# GPRS_A7.net
KiCad netlist of a schematic drawn in EAGLE
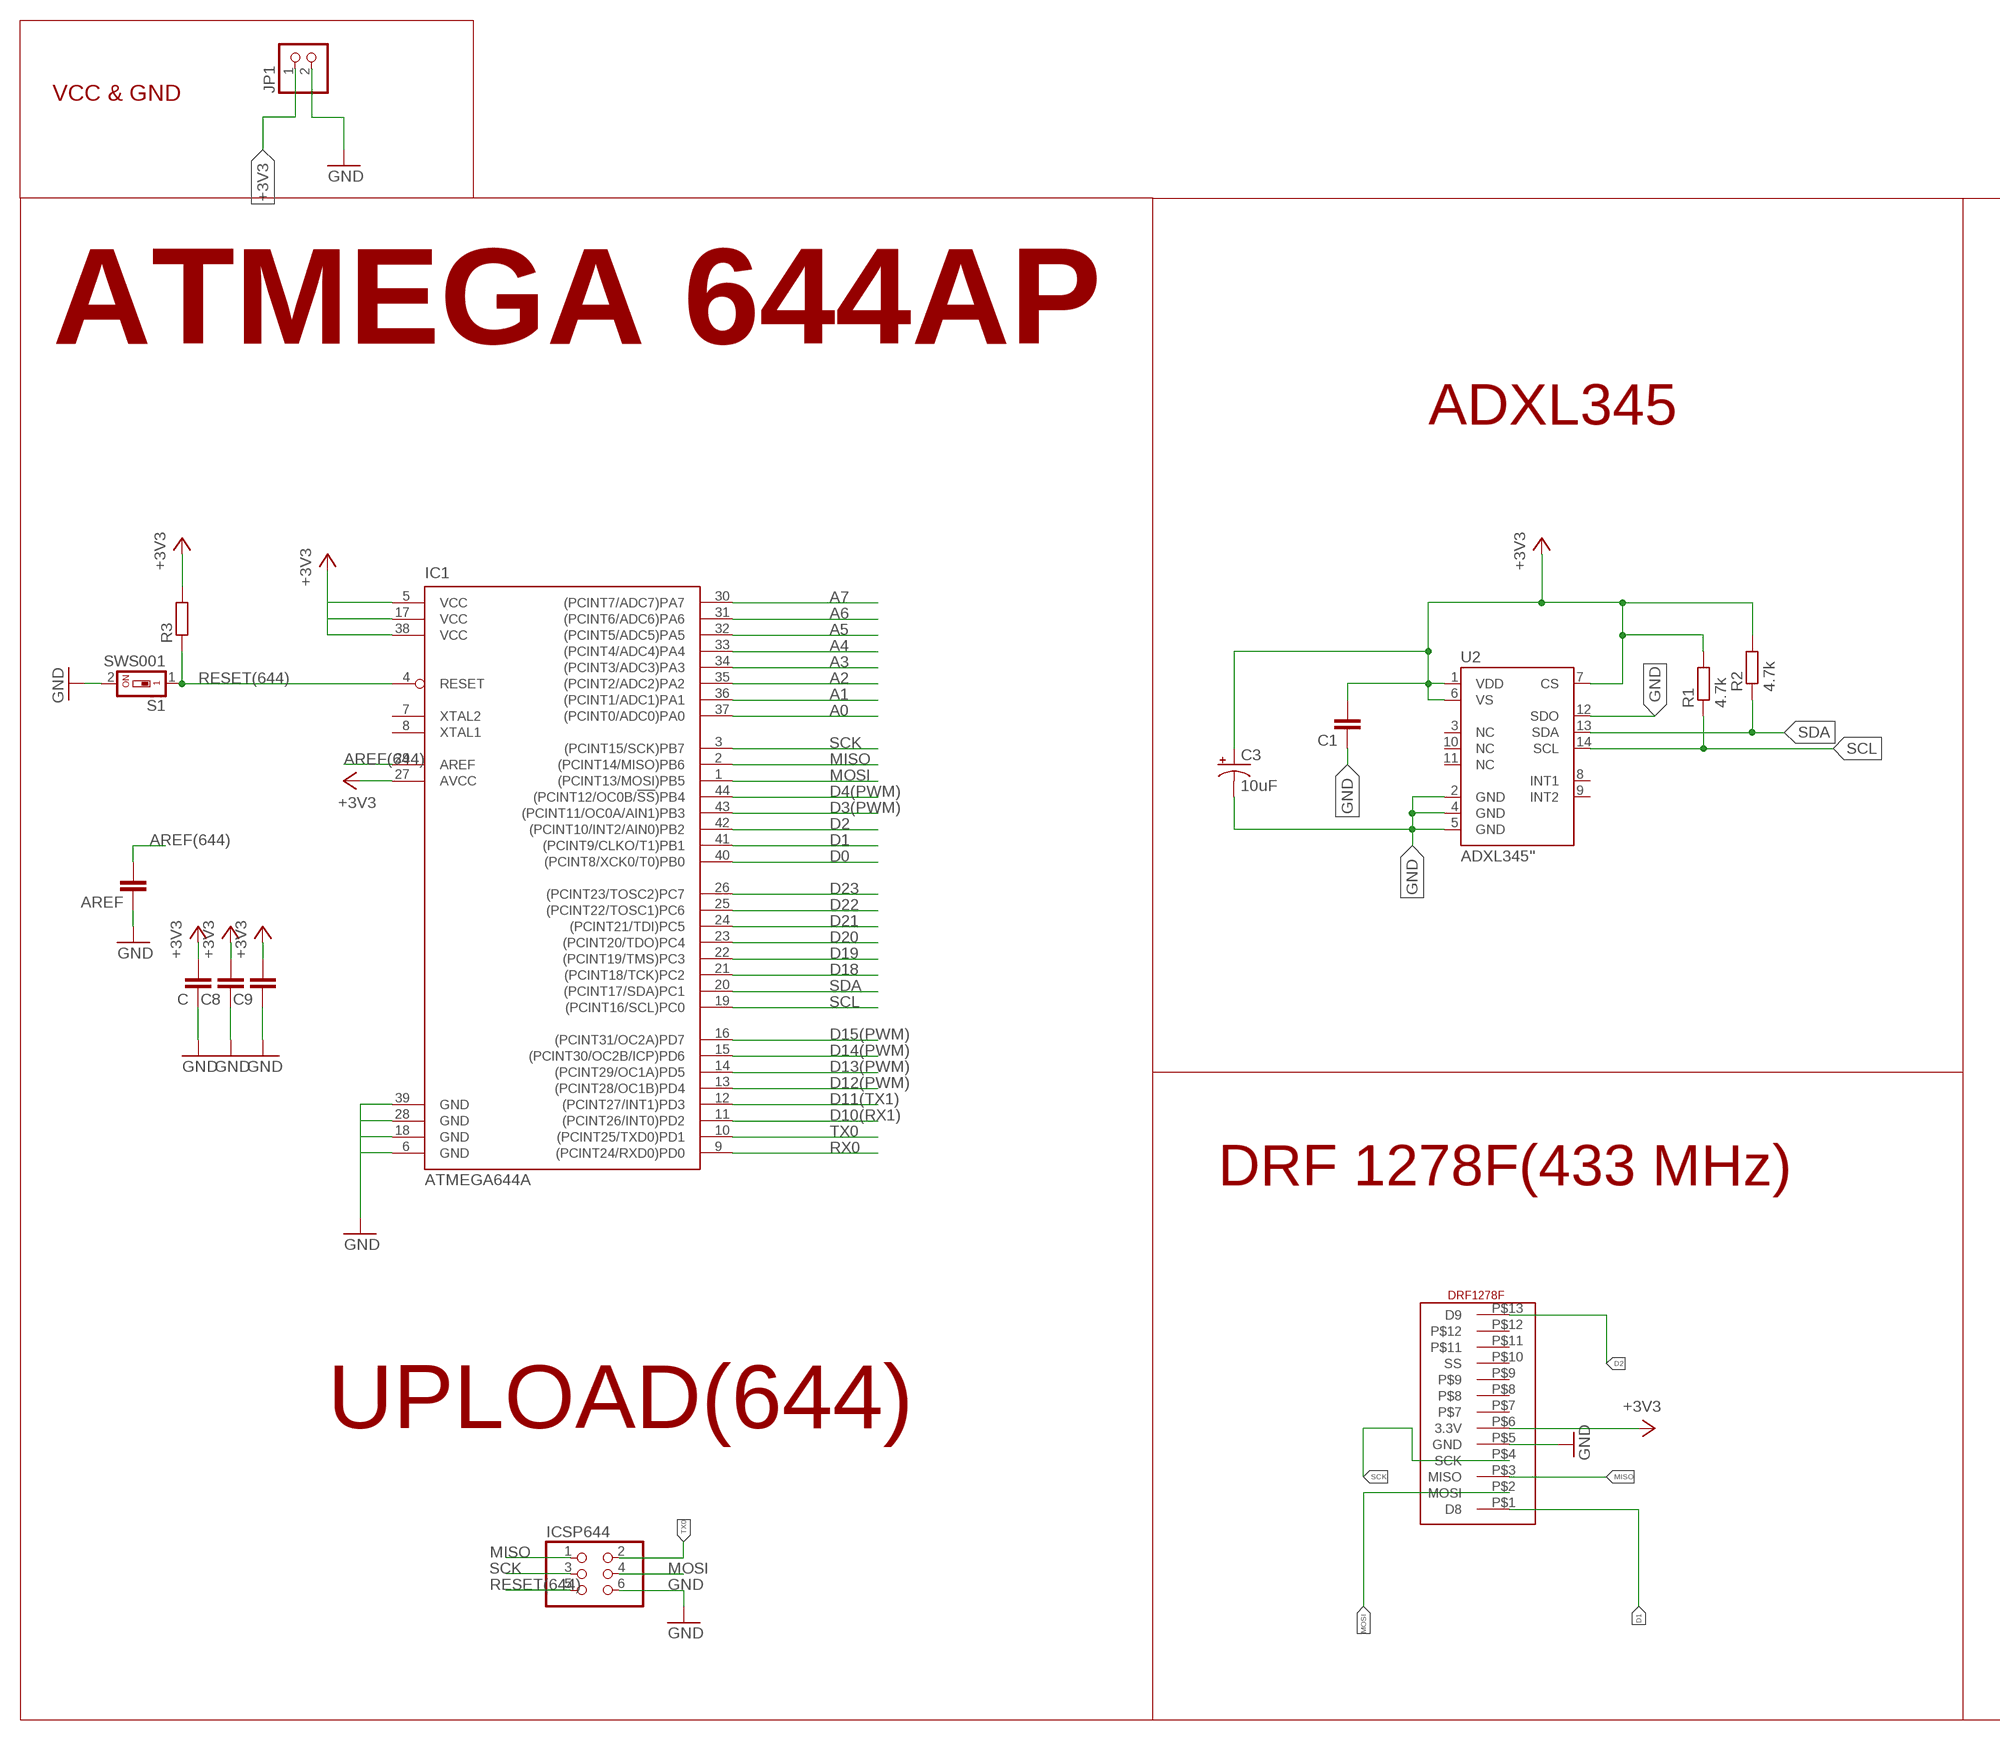
[diagram p0: schematic, sheet 1, part 1 of 2]
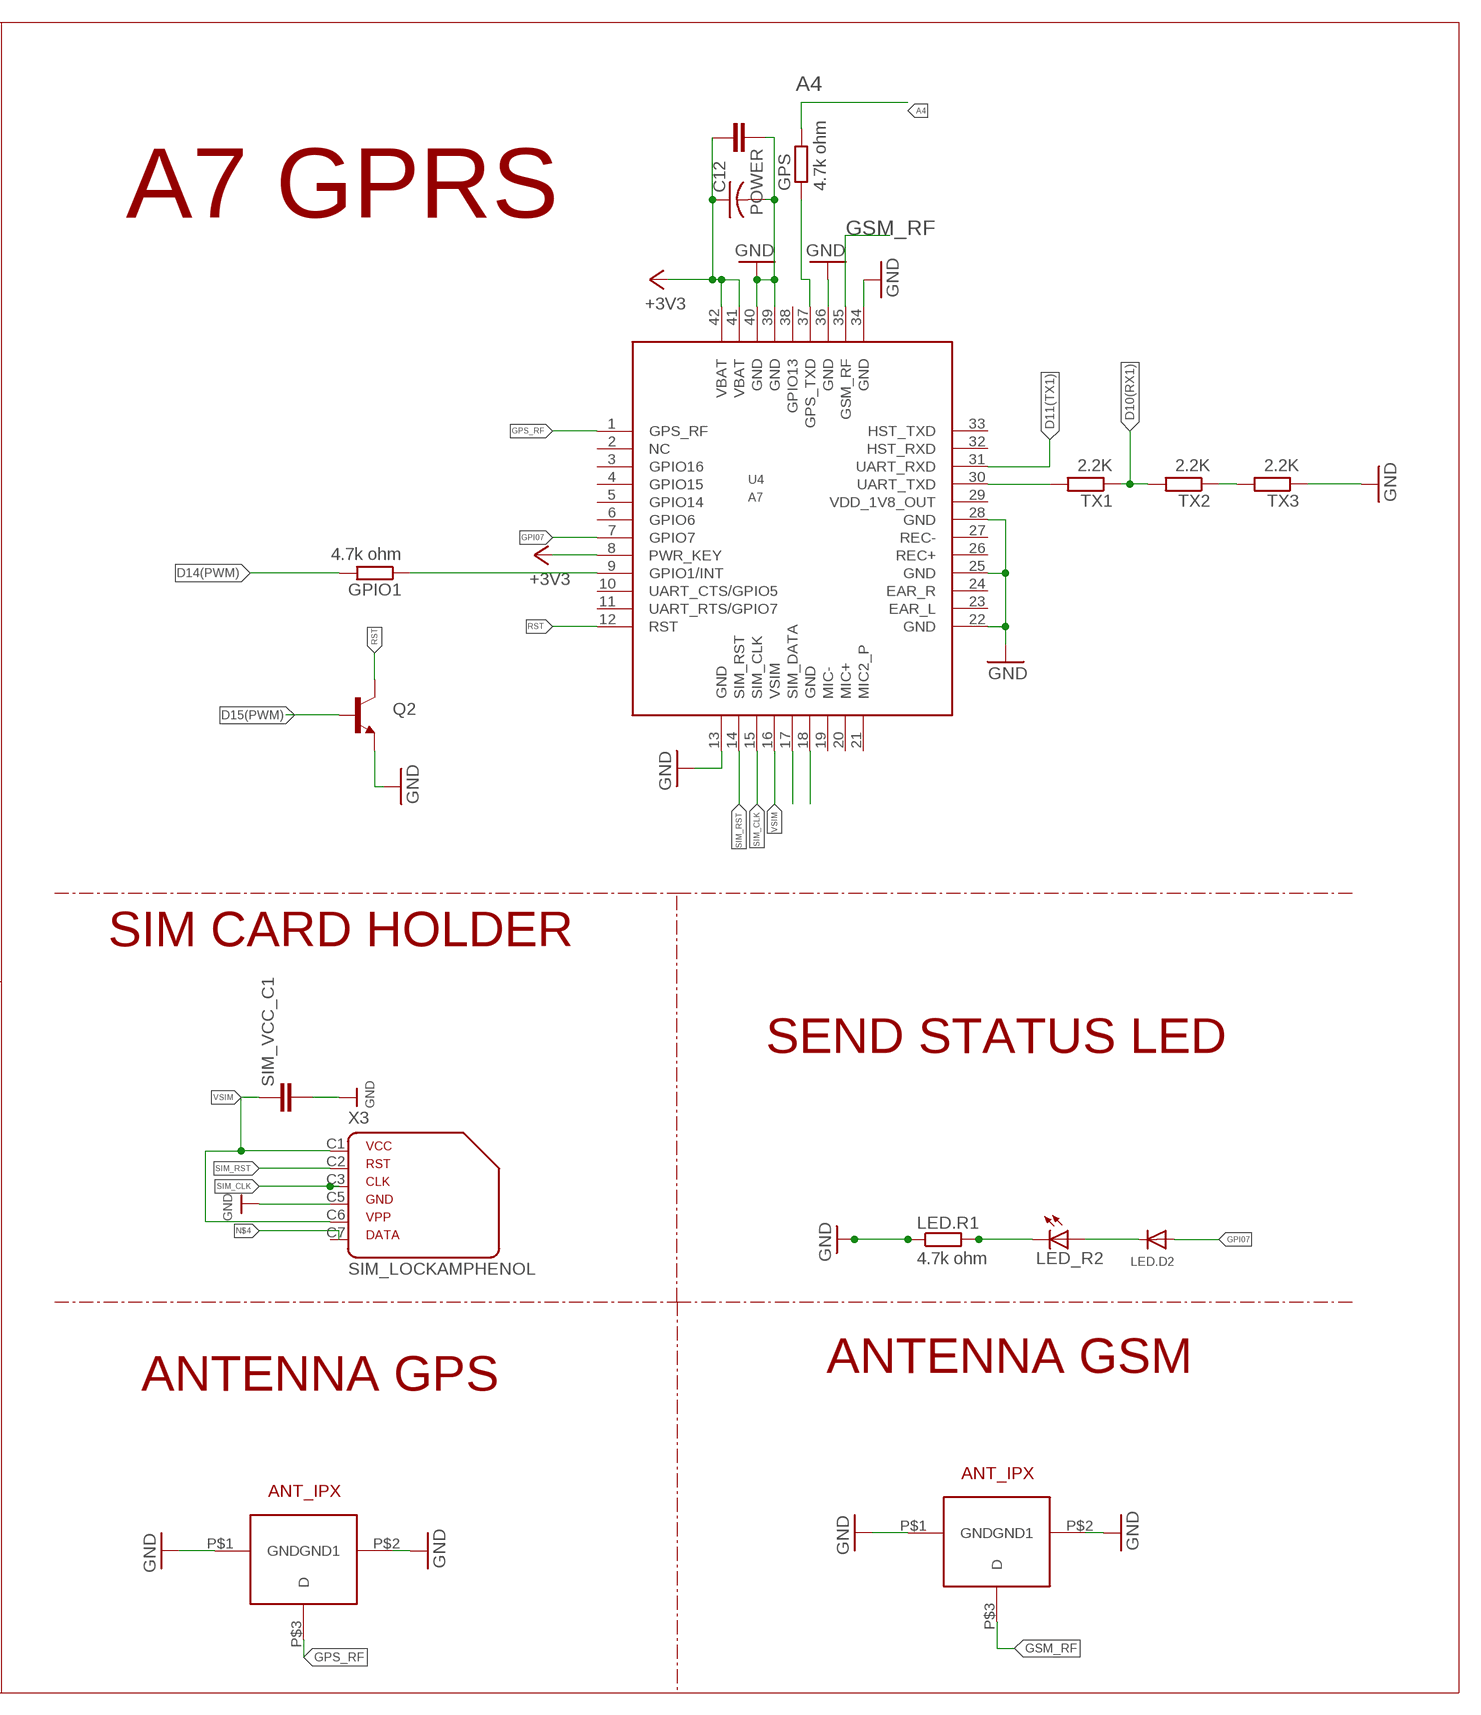
[diagram p1: schematic, sheet 1, part 2 of 2]

(export (version "E")
  (design (tool "Eeschema 10.0.6"))
  (components
    (comp (ref "AREF")
      (value "100nF")
      (footprint "eagle-import:C0805")
      (libsource (lib "eagle-import") (part "C-EUC0805"))
    )
    (comp (ref "C")
      (value "22 uF")
      (footprint "eagle-import:C0805")
      (libsource (lib "eagle-import") (part "C-EUC0805"))
    )
    (comp (ref "C1")
      (value "0.1uF")
      (footprint "eagle-import:C0805")
      (libsource (lib "eagle-import") (part "C-EUC0805"))
    )
    (comp (ref "C3")
      (value "10uF")
      (footprint "eagle-import:EIA3216")
      (libsource (lib "eagle-import") (part "CAP_POL1206"))
    )
    (comp (ref "C8")
      (value "100nF")
      (footprint "eagle-import:C0805")
      (libsource (lib "eagle-import") (part "C-EUC0805"))
    )
    (comp (ref "C9")
      (value "100nF")
      (footprint "eagle-import:C0805")
      (libsource (lib "eagle-import") (part "C-EUC0805"))
    )
    (comp (ref "C12")
      (value "C-US025-024X044")
      (footprint "eagle-import:C025-024X044")
      (libsource (lib "eagle-import") (part "C-US025-024X044"))
    )
    (comp (ref "GPIO1")
      (value "4.7k ohm")
      (footprint "eagle-import:R0805")
      (libsource (lib "eagle-import") (part "R-EU_R0805"))
    )
    (comp (ref "GPS")
      (value "4.7k ohm")
      (footprint "eagle-import:R0805")
      (libsource (lib "eagle-import") (part "R-EU_R0805"))
    )
    (comp (ref "IC1")
      (value "ATMEGA644A")
      (footprint "eagle-import:TQFP44")
      (fields (field (name "MPN") "ATMEGA644PV-10AU"))
      (libsource (lib "eagle-import") (part "ATMEGA644A"))
    )
    (comp (ref "ICSP644")
      (value "PINHD-2X3")
      (footprint "eagle-import:2X03")
      (libsource (lib "eagle-import") (part "PINHD-2X3"))
    )
    (comp (ref "JP1")
      (value "PINHD-1X2")
      (footprint "eagle-import:1X02")
      (libsource (lib "eagle-import") (part "PINHD-1X2"))
    )
    (comp (ref "LED.D2")
      (value "DIODESOD-123")
      (footprint "eagle-import:SOD-123")
      (libsource (lib "eagle-import") (part "DIODESOD-123"))
    )
    (comp (ref "LED.R1")
      (value "4.7k ohm")
      (footprint "eagle-import:R0805")
      (libsource (lib "eagle-import") (part "R-EU_R0805"))
    )
    (comp (ref "LED_R2")
      (value "LEDCHIP-LED0805")
      (footprint "eagle-import:CHIP-LED0805")
      (libsource (lib "eagle-import") (part "LEDCHIP-LED0805"))
    )
    (comp (ref "POWER")
      (value "100nF")
      (footprint "eagle-import:C0805")
      (libsource (lib "eagle-import") (part "C-EUC0805"))
    )
    (comp (ref "Q2")
      (value "TRANSISTOR_NPNSOT23-3")
      (footprint "eagle-import:SOT23-3")
      (libsource (lib "eagle-import") (part "TRANSISTOR_NPNSOT23-3"))
    )
    (comp (ref "R1")
      (value "4.7k")
      (footprint "eagle-import:R0805")
      (libsource (lib "eagle-import") (part "R-EU_R0805"))
    )
    (comp (ref "R2")
      (value "4.7k")
      (footprint "eagle-import:R0805")
      (libsource (lib "eagle-import") (part "R-EU_R0805"))
    )
    (comp (ref "R3")
      (value "R-EU_R0805")
      (footprint "eagle-import:R0805")
      (libsource (lib "eagle-import") (part "R-EU_R0805"))
    )
    (comp (ref "S1")
      (value "SWS001")
      (footprint "eagle-import:SMS-001")
      (libsource (lib "eagle-import") (part "SWS001"))
    )
    (comp (ref "SIM_VCC_C1")
      (value "100nF")
      (footprint "eagle-import:C0805")
      (libsource (lib "eagle-import") (part "C-EUC0805"))
    )
    (comp (ref "TX1")
      (value "2.2K")
      (footprint "eagle-import:R0805")
      (libsource (lib "eagle-import") (part "R-EU_R0805"))
    )
    (comp (ref "TX2")
      (value "2.2K")
      (footprint "eagle-import:R0805")
      (libsource (lib "eagle-import") (part "R-EU_R0805"))
    )
    (comp (ref "TX3")
      (value "2.2K")
      (footprint "eagle-import:R0805")
      (libsource (lib "eagle-import") (part "R-EU_R0805"))
    )
    (comp (ref "U$1")
      (value "DRF1278F")
      (footprint "eagle-import:DIP13")
      (libsource (lib "eagle-import") (part "DRF1278F"))
    )
    (comp (ref "U$2")
      (value "ANTENNA_IPX")
      (footprint "eagle-import:SMD3")
      (libsource (lib "eagle-import") (part "ANTENNA_IPX"))
    )
    (comp (ref "U$9")
      (value "ANTENNA_IPX")
      (footprint "eagle-import:SMD3")
      (libsource (lib "eagle-import") (part "ANTENNA_IPX"))
    )
    (comp (ref "U2")
      (value "ADXL345\"")
      (footprint "eagle-import:ADXL3451_1")
      (libsource (lib "eagle-import") (part "ADXL345{dblquote}"))
    )
    (comp (ref "U4") (value "A7") (footprint "eagle-import:A7") (libsource (lib "eagle-import") (part "A7")))
    (comp (ref "X3")
      (value "SIM_LOCKAMPHENOL")
      (footprint "eagle-import:C707_10M006_512_2")
      (libsource (lib "eagle-import") (part "SIM_LOCKAMPHENOL"))
    )
  )
  (nets
    (net (code "1") (name "+3V3") (class "Default")
      (node (ref "C") (pin "2") (pinfunction "2_2") (pintype "passive"))
      (node (ref "C1") (pin "2") (pinfunction "2_2") (pintype "passive"))
      (node (ref "C12") (pin "1") (pinfunction "1_1") (pintype "passive"))
      (node (ref "C3") (pin "A") (pinfunction "+_A") (pintype "passive"))
      (node (ref "C8") (pin "2") (pinfunction "2_2") (pintype "passive"))
      (node (ref "C9") (pin "2") (pinfunction "2_2") (pintype "passive"))
      (node (ref "IC1") (pin "17") (pinfunction "VCC_17") (pintype "power_in"))
      (node (ref "IC1") (pin "27") (pinfunction "AVCC_27") (pintype "power_in"))
      (node (ref "IC1") (pin "38") (pinfunction "VCC_38") (pintype "power_in"))
      (node (ref "IC1") (pin "5") (pinfunction "VCC_5") (pintype "power_in"))
      (node (ref "JP1") (pin "1") (pinfunction "1_1") (pintype "passive"))
      (node (ref "POWER") (pin "2") (pinfunction "2_2") (pintype "passive"))
      (node (ref "R1") (pin "2") (pinfunction "2_2") (pintype "passive"))
      (node (ref "R2") (pin "2") (pinfunction "2_2") (pintype "passive"))
      (node (ref "R3") (pin "2") (pinfunction "2_2") (pintype "passive"))
      (node (ref "U$1") (pin "P$6") (pinfunction "3.3V_P$6") (pintype "bidirectional"))
      (node (ref "U2") (pin "1") (pinfunction "VDD_1") (pintype "bidirectional"))
      (node (ref "U2") (pin "6") (pinfunction "VS_6") (pintype "bidirectional"))
      (node (ref "U2") (pin "7") (pinfunction "CS_7") (pintype "bidirectional"))
      (node (ref "U4") (pin "41") (pinfunction "VBAT_41") (pintype "bidirectional"))
      (node (ref "U4") (pin "42") (pinfunction "VBAT_42") (pintype "bidirectional"))
      (node (ref "U4") (pin "8") (pinfunction "PWR_KEY_8") (pintype "bidirectional"))
    )
    (net (code "2") (name "/A0") (class "Default")
      (node (ref "IC1") (pin "37") (pinfunction "(PCINT0/ADC0)PA0_37") (pintype "bidirectional"))
    )
    (net (code "3") (name "/A1") (class "Default")
      (node (ref "IC1") (pin "36") (pinfunction "(PCINT1/ADC1)PA1_36") (pintype "bidirectional"))
    )
    (net (code "4") (name "/A2") (class "Default")
      (node (ref "IC1") (pin "35") (pinfunction "(PCINT2/ADC2)PA2_35") (pintype "bidirectional"))
    )
    (net (code "5") (name "/A3") (class "Default")
      (node (ref "IC1") (pin "34") (pinfunction "(PCINT3/ADC3)PA3_34") (pintype "bidirectional"))
    )
    (net (code "6") (name "/A5") (class "Default")
      (node (ref "IC1") (pin "32") (pinfunction "(PCINT5/ADC5)PA5_32") (pintype "bidirectional"))
    )
    (net (code "7") (name "/A6") (class "Default")
      (node (ref "IC1") (pin "31") (pinfunction "(PCINT6/ADC6)PA6_31") (pintype "bidirectional"))
    )
    (net (code "8") (name "/A7") (class "Default")
      (node (ref "IC1") (pin "30") (pinfunction "(PCINT7/ADC7)PA7_30") (pintype "bidirectional"))
    )
    (net (code "9") (name "/AREF(644)") (class "Default")
      (node (ref "AREF") (pin "2") (pinfunction "2_2") (pintype "passive"))
      (node (ref "IC1") (pin "29") (pinfunction "AREF_29") (pintype "passive"))
    )
    (net (code "10") (name "/D0") (class "Default")
      (node (ref "IC1") (pin "40") (pinfunction "(PCINT8/XCK0/T0)PB0_40") (pintype "bidirectional"))
    )
    (net (code "11") (name "/D3(PWM)") (class "Default")
      (node (ref "IC1") (pin "43") (pinfunction "(PCINT11/OC0A/AIN1)PB3_43") (pintype "bidirectional"))
    )
    (net (code "12") (name "/D4(PWM)") (class "Default")
      (node (ref "IC1") (pin "44") (pinfunction "(PCINT12/OC0B/~{SS})PB4_44") (pintype "bidirectional"))
    )
    (net (code "13") (name "/D12(PWM)") (class "Default")
      (node (ref "IC1") (pin "13") (pinfunction "(PCINT28/OC1B)PD4_13") (pintype "bidirectional"))
    )
    (net (code "14") (name "/D13(PWM)") (class "Default")
      (node (ref "IC1") (pin "14") (pinfunction "(PCINT29/OC1A)PD5_14") (pintype "bidirectional"))
    )
    (net (code "15") (name "/D18") (class "Default")
      (node (ref "IC1") (pin "21") (pinfunction "(PCINT18/TCK)PC2_21") (pintype "output"))
    )
    (net (code "16") (name "/D19") (class "Default")
      (node (ref "IC1") (pin "22") (pinfunction "(PCINT19/TMS)PC3_22") (pintype "output"))
    )
    (net (code "17") (name "/D20") (class "Default")
      (node (ref "IC1") (pin "23") (pinfunction "(PCINT20/TDO)PC4_23") (pintype "output"))
    )
    (net (code "18") (name "/D21") (class "Default")
      (node (ref "IC1") (pin "24") (pinfunction "(PCINT21/TDI)PC5_24") (pintype "output"))
    )
    (net (code "19") (name "/D22") (class "Default")
      (node (ref "IC1") (pin "25") (pinfunction "(PCINT22/TOSC1)PC6_25") (pintype "output"))
    )
    (net (code "20") (name "/D23") (class "Default")
      (node (ref "IC1") (pin "26") (pinfunction "(PCINT23/TOSC2)PC7_26") (pintype "output"))
    )
    (net (code "21") (name "/RESET(644)") (class "Default")
      (node (ref "IC1") (pin "4") (pinfunction "RESET_4") (pintype "input"))
      (node (ref "ICSP644") (pin "5") (pinfunction "5_5") (pintype "passive"))
      (node (ref "R3") (pin "1") (pinfunction "1_1") (pintype "passive"))
      (node (ref "S1") (pin "1") (pinfunction "1_1") (pintype "passive"))
    )
    (net (code "22") (name "/RX0") (class "Default")
      (node (ref "IC1") (pin "9") (pinfunction "(PCINT24/RXD0)PD0_9") (pintype "bidirectional"))
    )
    (net (code "23") (name "A4") (class "Default")
      (node (ref "GPS") (pin "2") (pinfunction "2_2") (pintype "passive"))
      (node (ref "IC1") (pin "33") (pinfunction "(PCINT4/ADC4)PA4_33") (pintype "bidirectional"))
    )
    (net (code "24") (name "D1") (class "Default")
      (node (ref "IC1") (pin "41") (pinfunction "(PCINT9/CLKO/T1)PB1_41") (pintype "bidirectional"))
      (node (ref "U$1") (pin "P$1") (pinfunction "D8_P$1") (pintype "bidirectional"))
    )
    (net (code "25") (name "D2") (class "Default")
      (node (ref "IC1") (pin "42") (pinfunction "(PCINT10/INT2/AIN0)PB2_42") (pintype "bidirectional"))
      (node (ref "U$1") (pin "P$13") (pinfunction "D9_P$13") (pintype "bidirectional"))
    )
    (net (code "26") (name "D10(RX1)") (class "Default")
      (node (ref "IC1") (pin "11") (pinfunction "(PCINT26/INT0)PD2_11") (pintype "bidirectional"))
      (node (ref "TX1") (pin "1") (pinfunction "1_1") (pintype "passive"))
      (node (ref "TX2") (pin "2") (pinfunction "2_2") (pintype "passive"))
    )
    (net (code "27") (name "D11(TX1)") (class "Default")
      (node (ref "IC1") (pin "12") (pinfunction "(PCINT27/INT1)PD3_12") (pintype "bidirectional"))
      (node (ref "U4") (pin "31") (pinfunction "UART_RXD_31") (pintype "bidirectional"))
    )
    (net (code "28") (name "D14(PWM)") (class "Default")
      (node (ref "GPIO1") (pin "2") (pinfunction "2_2") (pintype "passive"))
      (node (ref "IC1") (pin "15") (pinfunction "(PCINT30/OC2B/ICP)PD6_15") (pintype "bidirectional"))
    )
    (net (code "29") (name "D15(PWM)") (class "Default")
      (node (ref "IC1") (pin "16") (pinfunction "(PCINT31/OC2A)PD7_16") (pintype "bidirectional"))
      (node (ref "Q2") (pin "1") (pinfunction "B_1") (pintype "passive"))
    )
    (net (code "30") (name "GND") (class "Default")
      (node (ref "AREF") (pin "1") (pinfunction "1_1") (pintype "passive"))
      (node (ref "C") (pin "1") (pinfunction "1_1") (pintype "passive"))
      (node (ref "C1") (pin "1") (pinfunction "1_1") (pintype "passive"))
      (node (ref "C12") (pin "2") (pinfunction "2_2") (pintype "passive"))
      (node (ref "C3") (pin "C") (pinfunction "-_C") (pintype "passive"))
      (node (ref "C8") (pin "1") (pinfunction "1_1") (pintype "passive"))
      (node (ref "C9") (pin "1") (pinfunction "1_1") (pintype "passive"))
      (node (ref "IC1") (pin "18") (pinfunction "GND_18") (pintype "power_in"))
      (node (ref "IC1") (pin "28") (pinfunction "GND_28") (pintype "power_in"))
      (node (ref "IC1") (pin "39") (pinfunction "GND_39") (pintype "power_in"))
      (node (ref "IC1") (pin "6") (pinfunction "GND_6") (pintype "power_in"))
      (node (ref "ICSP644") (pin "6") (pinfunction "6_6") (pintype "passive"))
      (node (ref "JP1") (pin "2") (pinfunction "2_2") (pintype "passive"))
      (node (ref "LED.R1") (pin "1") (pinfunction "1_1") (pintype "passive"))
      (node (ref "POWER") (pin "1") (pinfunction "1_1") (pintype "passive"))
      (node (ref "Q2") (pin "2") (pinfunction "E_2") (pintype "passive"))
      (node (ref "S1") (pin "2") (pinfunction "2_2") (pintype "passive"))
      (node (ref "SIM_VCC_C1") (pin "2") (pinfunction "2_2") (pintype "passive"))
      (node (ref "TX3") (pin "1") (pinfunction "1_1") (pintype "passive"))
      (node (ref "U$1") (pin "P$5") (pinfunction "GND_P$5") (pintype "bidirectional"))
      (node (ref "U$2") (pin "P$1") (pinfunction "GND_P$1") (pintype "bidirectional"))
      (node (ref "U$2") (pin "P$2") (pinfunction "GND1_P$2") (pintype "bidirectional"))
      (node (ref "U$9") (pin "P$1") (pinfunction "GND_P$1") (pintype "bidirectional"))
      (node (ref "U$9") (pin "P$2") (pinfunction "GND1_P$2") (pintype "bidirectional"))
      (node (ref "U2") (pin "12") (pinfunction "SDO_12") (pintype "bidirectional"))
      (node (ref "U2") (pin "2") (pinfunction "GND_2") (pintype "bidirectional"))
      (node (ref "U2") (pin "4") (pinfunction "GND_4") (pintype "bidirectional"))
      (node (ref "U2") (pin "5") (pinfunction "GND_5") (pintype "bidirectional"))
      (node (ref "U4") (pin "13") (pinfunction "GND_13") (pintype "bidirectional"))
      (node (ref "U4") (pin "22") (pinfunction "GND_22") (pintype "bidirectional"))
      (node (ref "U4") (pin "25") (pinfunction "GND_25") (pintype "bidirectional"))
      (node (ref "U4") (pin "28") (pinfunction "GND_28") (pintype "bidirectional"))
      (node (ref "U4") (pin "34") (pinfunction "GND_34") (pintype "bidirectional"))
      (node (ref "U4") (pin "36") (pinfunction "GND_36") (pintype "bidirectional"))
      (node (ref "U4") (pin "39") (pinfunction "GND_39") (pintype "bidirectional"))
      (node (ref "U4") (pin "40") (pinfunction "GND_40") (pintype "bidirectional"))
      (node (ref "X3") (pin "C5") (pinfunction "4_C5") (pintype "passive"))
    )
    (net (code "31") (name "GPI07") (class "Default")
      (node (ref "LED.D2") (pin "A") (pinfunction "A_A") (pintype "passive"))
      (node (ref "U4") (pin "7") (pinfunction "GPIO7_7") (pintype "bidirectional"))
    )
    (net (code "32") (name "GPS_RF") (class "Default")
      (node (ref "U$2") (pin "P$3") (pinfunction "D_P$3") (pintype "bidirectional"))
      (node (ref "U4") (pin "1") (pinfunction "GPS_RF_1") (pintype "bidirectional"))
    )
    (net (code "33") (name "GSM_RF") (class "Default")
      (node (ref "U$9") (pin "P$3") (pinfunction "D_P$3") (pintype "bidirectional"))
      (node (ref "U4") (pin "35") (pinfunction "GSM_RF_35") (pintype "bidirectional"))
    )
    (net (code "34") (name "MISO") (class "Default")
      (node (ref "IC1") (pin "2") (pinfunction "(PCINT14/MISO)PB6_2") (pintype "bidirectional"))
      (node (ref "ICSP644") (pin "1") (pinfunction "1_1") (pintype "passive"))
      (node (ref "U$1") (pin "P$3") (pinfunction "MISO_P$3") (pintype "bidirectional"))
    )
    (net (code "35") (name "MOSI") (class "Default")
      (node (ref "IC1") (pin "1") (pinfunction "(PCINT13/MOSI)PB5_1") (pintype "bidirectional"))
      (node (ref "ICSP644") (pin "4") (pinfunction "4_4") (pintype "passive"))
      (node (ref "U$1") (pin "P$2") (pinfunction "MOSI_P$2") (pintype "bidirectional"))
    )
    (net (code "37") (name "Net-(LED.D2-PadC)") (class "Default")
      (node (ref "LED.D2") (pin "C") (pinfunction "C_C") (pintype "passive"))
      (node (ref "LED_R2") (pin "A") (pinfunction "A_A") (pintype "passive"))
    )
    (net (code "38") (name "Net-(LED.R1-Pad2)") (class "Default")
      (node (ref "LED.R1") (pin "2") (pinfunction "2_2") (pintype "passive"))
      (node (ref "LED_R2") (pin "C") (pinfunction "C_C") (pintype "passive"))
    )
    (net (code "39") (name "Net-(TX2-Pad1)") (class "Default")
      (node (ref "TX2") (pin "1") (pinfunction "1_1") (pintype "passive"))
      (node (ref "TX3") (pin "2") (pinfunction "2_2") (pintype "passive"))
    )
    (net (code "40") (name "Net-(U4-GPIO1{slash}INT)") (class "Default")
      (node (ref "GPIO1") (pin "1") (pinfunction "1_1") (pintype "passive"))
      (node (ref "U4") (pin "9") (pinfunction "GPIO1/INT_9") (pintype "bidirectional"))
    )
    (net (code "41") (name "Net-(U4-GPS_TXD)") (class "Default")
      (node (ref "GPS") (pin "1") (pinfunction "1_1") (pintype "passive"))
      (node (ref "U4") (pin "37") (pinfunction "GPS_TXD_37") (pintype "bidirectional"))
    )
    (net (code "42") (name "Net-(U4-UART_TXD)") (class "Default")
      (node (ref "TX1") (pin "2") (pinfunction "2_2") (pintype "passive"))
      (node (ref "U4") (pin "30") (pinfunction "UART_TXD_30") (pintype "bidirectional"))
    )
    (net (code "43") (name "RST") (class "Default")
      (node (ref "Q2") (pin "3") (pinfunction "C_3") (pintype "passive"))
      (node (ref "U4") (pin "12") (pinfunction "RST_12") (pintype "bidirectional"))
    )
    (net (code "44") (name "SCK") (class "Default")
      (node (ref "IC1") (pin "3") (pinfunction "(PCINT15/SCK)PB7_3") (pintype "bidirectional"))
      (node (ref "ICSP644") (pin "3") (pinfunction "3_3") (pintype "passive"))
      (node (ref "U$1") (pin "P$4") (pinfunction "SCK_P$4") (pintype "bidirectional"))
    )
    (net (code "45") (name "SCL") (class "Default")
      (node (ref "IC1") (pin "19") (pinfunction "(PCINT16/SCL)PC0_19") (pintype "output"))
      (node (ref "R1") (pin "1") (pinfunction "1_1") (pintype "passive"))
      (node (ref "U2") (pin "14") (pinfunction "SCL_14") (pintype "bidirectional"))
    )
    (net (code "46") (name "SDA") (class "Default")
      (node (ref "IC1") (pin "20") (pinfunction "(PCINT17/SDA)PC1_20") (pintype "output"))
      (node (ref "R2") (pin "1") (pinfunction "1_1") (pintype "passive"))
      (node (ref "U2") (pin "13") (pinfunction "SDA_13") (pintype "bidirectional"))
    )
    (net (code "47") (name "SIM_CLK") (class "Default")
      (node (ref "U4") (pin "15") (pinfunction "SIM_CLK_15") (pintype "bidirectional"))
      (node (ref "X3") (pin "C3") (pinfunction "3_C3") (pintype "passive"))
    )
    (net (code "48") (name "SIM_RST") (class "Default")
      (node (ref "U4") (pin "14") (pinfunction "SIM_RST_14") (pintype "bidirectional"))
      (node (ref "X3") (pin "C2") (pinfunction "2_C2") (pintype "passive"))
    )
    (net (code "49") (name "TX0") (class "Default")
      (node (ref "IC1") (pin "10") (pinfunction "(PCINT25/TXD0)PD1_10") (pintype "bidirectional"))
      (node (ref "ICSP644") (pin "2") (pinfunction "2_2") (pintype "passive"))
    )
    (net (code "50") (name "VSIM") (class "Default")
      (node (ref "SIM_VCC_C1") (pin "1") (pinfunction "1_1") (pintype "passive"))
      (node (ref "U4") (pin "16") (pinfunction "VSIM_16") (pintype "bidirectional"))
      (node (ref "X3") (pin "C1") (pinfunction "1_C1") (pintype "passive"))
      (node (ref "X3") (pin "C6") (pinfunction "5_C6") (pintype "passive"))
    )
    (net (code "51") (name "unconnected-(IC1-XTAL1-Pad8)") (class "Default")
      (node (ref "IC1") (pin "8") (pinfunction "XTAL1_8") (pintype "bidirectional"))
    )
    (net (code "52") (name "unconnected-(IC1-XTAL2-Pad7)") (class "Default")
      (node (ref "IC1") (pin "7") (pinfunction "XTAL2_7") (pintype "bidirectional"))
    )
    (net (code "53") (name "unconnected-(U$1-PadP$7)") (class "Default")
      (node (ref "U$1") (pin "P$7") (pinfunction "P$7_P$7") (pintype "bidirectional"))
    )
    (net (code "54") (name "unconnected-(U$1-PadP$8)") (class "Default")
      (node (ref "U$1") (pin "P$8") (pinfunction "P$8_P$8") (pintype "bidirectional"))
    )
    (net (code "55") (name "unconnected-(U$1-PadP$9)") (class "Default")
      (node (ref "U$1") (pin "P$9") (pinfunction "P$9_P$9") (pintype "bidirectional"))
    )
    (net (code "56") (name "unconnected-(U$1-PadP$11)") (class "Default")
      (node (ref "U$1") (pin "P$11") (pinfunction "P$11_P$11") (pintype "bidirectional"))
    )
    (net (code "57") (name "unconnected-(U$1-PadP$12)") (class "Default")
      (node (ref "U$1") (pin "P$12") (pinfunction "P$12_P$12") (pintype "bidirectional"))
    )
    (net (code "58") (name "unconnected-(U$1-SS-PadP$10)") (class "Default")
      (node (ref "U$1") (pin "P$10") (pinfunction "SS_P$10") (pintype "bidirectional"))
    )
    (net (code "59") (name "unconnected-(U2-INT1-Pad8)") (class "Default")
      (node (ref "U2") (pin "8") (pinfunction "INT1_8") (pintype "bidirectional"))
    )
    (net (code "60") (name "unconnected-(U2-INT2-Pad9)") (class "Default")
      (node (ref "U2") (pin "9") (pinfunction "INT2_9") (pintype "bidirectional"))
    )
    (net (code "61") (name "unconnected-(U2-NC-Pad3)") (class "Default")
      (node (ref "U2") (pin "3") (pinfunction "NC_3") (pintype "bidirectional"))
    )
    (net (code "62") (name "unconnected-(U2-NC-Pad10)") (class "Default")
      (node (ref "U2") (pin "10") (pinfunction "NC_10") (pintype "bidirectional"))
    )
    (net (code "63") (name "unconnected-(U2-NC-Pad11)") (class "Default")
      (node (ref "U2") (pin "11") (pinfunction "NC_11") (pintype "bidirectional"))
    )
    (net (code "64") (name "unconnected-(U4-EAR_L-Pad23)") (class "Default")
      (node (ref "U4") (pin "23") (pinfunction "EAR_L_23") (pintype "bidirectional"))
    )
    (net (code "65") (name "unconnected-(U4-EAR_R-Pad24)") (class "Default")
      (node (ref "U4") (pin "24") (pinfunction "EAR_R_24") (pintype "bidirectional"))
    )
    (net (code "66") (name "unconnected-(U4-GND-Pad18)") (class "Default")
      (node (ref "U4") (pin "18") (pinfunction "GND_18") (pintype "bidirectional"))
    )
    (net (code "67") (name "unconnected-(U4-GPIO6-Pad6)") (class "Default")
      (node (ref "U4") (pin "6") (pinfunction "GPIO6_6") (pintype "bidirectional"))
    )
    (net (code "68") (name "unconnected-(U4-GPIO13-Pad38)") (class "Default")
      (node (ref "U4") (pin "38") (pinfunction "GPIO13_38") (pintype "bidirectional"))
    )
    (net (code "69") (name "unconnected-(U4-GPIO14-Pad5)") (class "Default")
      (node (ref "U4") (pin "5") (pinfunction "GPIO14_5") (pintype "bidirectional"))
    )
    (net (code "70") (name "unconnected-(U4-GPIO15-Pad4)") (class "Default")
      (node (ref "U4") (pin "4") (pinfunction "GPIO15_4") (pintype "bidirectional"))
    )
    (net (code "71") (name "unconnected-(U4-GPIO16-Pad3)") (class "Default")
      (node (ref "U4") (pin "3") (pinfunction "GPIO16_3") (pintype "bidirectional"))
    )
    (net (code "72") (name "unconnected-(U4-HST_RXD-Pad32)") (class "Default")
      (node (ref "U4") (pin "32") (pinfunction "HST_RXD_32") (pintype "bidirectional"))
    )
    (net (code "73") (name "unconnected-(U4-HST_TXD-Pad33)") (class "Default")
      (node (ref "U4") (pin "33") (pinfunction "HST_TXD_33") (pintype "bidirectional"))
    )
    (net (code "74") (name "unconnected-(U4-MIC+-Pad20)") (class "Default")
      (node (ref "U4") (pin "20") (pinfunction "MIC+_20") (pintype "bidirectional"))
    )
    (net (code "75") (name "unconnected-(U4-MIC--Pad19)") (class "Default")
      (node (ref "U4") (pin "19") (pinfunction "MIC-_19") (pintype "bidirectional"))
    )
    (net (code "76") (name "unconnected-(U4-MIC2_P-Pad21)") (class "Default")
      (node (ref "U4") (pin "21") (pinfunction "MIC2_P_21") (pintype "bidirectional"))
    )
    (net (code "77") (name "unconnected-(U4-NC-Pad2)") (class "Default")
      (node (ref "U4") (pin "2") (pinfunction "NC_2") (pintype "bidirectional"))
    )
    (net (code "78") (name "unconnected-(U4-REC+-Pad26)") (class "Default")
      (node (ref "U4") (pin "26") (pinfunction "REC+_26") (pintype "bidirectional"))
    )
    (net (code "79") (name "unconnected-(U4-REC--Pad27)") (class "Default")
      (node (ref "U4") (pin "27") (pinfunction "REC-_27") (pintype "bidirectional"))
    )
    (net (code "80") (name "unconnected-(U4-SIM_DATA-Pad17)") (class "Default")
      (node (ref "U4") (pin "17") (pinfunction "SIM_DATA_17") (pintype "bidirectional"))
    )
    (net (code "81") (name "unconnected-(U4-UART_CTS{slash}GPIO5-Pad10)") (class "Default")
      (node (ref "U4") (pin "10") (pinfunction "UART_CTS/GPIO5_10") (pintype "bidirectional"))
    )
    (net (code "82") (name "unconnected-(U4-UART_RTS{slash}GPIO7-Pad11)") (class "Default")
      (node (ref "U4") (pin "11") (pinfunction "UART_RTS/GPIO7_11") (pintype "bidirectional"))
    )
    (net (code "83") (name "unconnected-(U4-VDD_1V8_OUT-Pad29)") (class "Default")
      (node (ref "U4") (pin "29") (pinfunction "VDD_1V8_OUT_29") (pintype "bidirectional"))
    )
    (net (code "84") (name "unconnected-(X3-6-PadC7)") (class "Default")
      (node (ref "X3") (pin "C7") (pinfunction "6_C7") (pintype "passive"))
    )
  )
)
